# CPU.net
KiCad netlist of a schematic drawn in Altium Designer
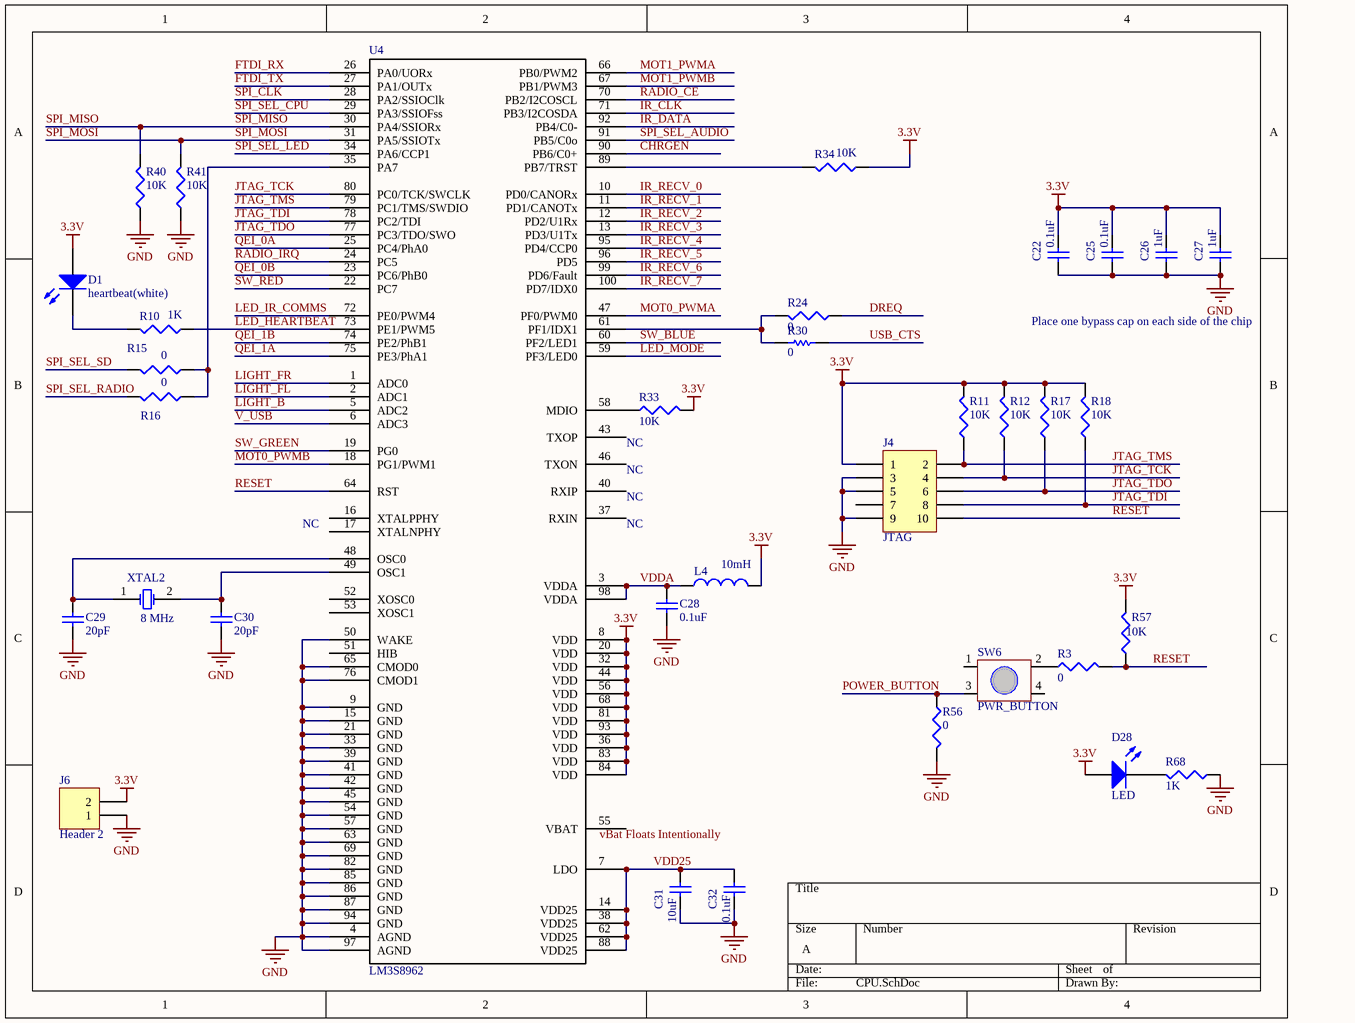
[diagram p0: CPU.SchDoc]

(export (version "E")
  (design (tool "Eeschema 10.0.6"))
  (components
    (comp (ref "C22")
      (value "0.1uF")
      (footprint "CAPC1005L")
      (description "Capacitor (Semiconductor SIM Model)")
      (fields (field (name "Comment") "Cap Semi") (field (name "PUBLISHER") "Altium Limited"))
      (libsource (lib "Miscellaneous Devices") (part "Cap Semi"))
    )
    (comp (ref "C25")
      (value "0.1uF")
      (footprint "CAPC1005L")
      (description "Capacitor (Semiconductor SIM Model)")
      (fields (field (name "Comment") "Cap Semi") (field (name "PUBLISHER") "Altium Limited"))
      (libsource (lib "Miscellaneous Devices") (part "Cap Semi"))
    )
    (comp (ref "C26")
      (value "1uF")
      (footprint "CAPC1608L")
      (description "Capacitor (Semiconductor SIM Model)")
      (fields (field (name "Comment") "Cap Semi") (field (name "PUBLISHER") "Altium Limited"))
      (libsource (lib "Miscellaneous Devices") (part "Cap Semi"))
    )
    (comp (ref "C27")
      (value "1uF")
      (footprint "CAPC1608L")
      (description "Capacitor (Semiconductor SIM Model)")
      (fields (field (name "Comment") "Cap Semi") (field (name "PUBLISHER") "Altium Limited"))
      (libsource (lib "Miscellaneous Devices") (part "Cap Semi"))
    )
    (comp (ref "C28")
      (value "0.1uF")
      (footprint "CAPC1005L")
      (description "Capacitor (Semiconductor SIM Model)")
      (fields (field (name "Comment") "Cap Semi") (field (name "PUBLISHER") "Altium Limited"))
      (libsource (lib "Miscellaneous Devices") (part "Cap Semi"))
    )
    (comp (ref "C29")
      (value "20pF")
      (footprint "CAPC1005L")
      (description "Capacitor (Semiconductor SIM Model)")
      (fields (field (name "Comment") "Cap Semi") (field (name "PUBLISHER") "Altium Limited"))
      (libsource (lib "Miscellaneous Devices") (part "Cap Semi"))
    )
    (comp (ref "C30")
      (value "20pF")
      (footprint "CAPC1005L")
      (description "Capacitor (Semiconductor SIM Model)")
      (fields (field (name "Comment") "Cap Semi") (field (name "PUBLISHER") "Altium Limited"))
      (libsource (lib "Miscellaneous Devices") (part "Cap Semi"))
    )
    (comp (ref "C31")
      (value "10uF")
      (footprint "CAPC1608L")
      (description "Capacitor (Semiconductor SIM Model)")
      (fields (field (name "Comment") "Cap Semi") (field (name "PUBLISHER") "Altium Limited"))
      (libsource (lib "Miscellaneous Devices") (part "Cap Semi"))
    )
    (comp (ref "C32")
      (value "0.1uF")
      (footprint "CAPC1005L")
      (description "Capacitor (Semiconductor SIM Model)")
      (fields (field (name "Comment") "Cap Semi") (field (name "PUBLISHER") "Altium Limited"))
      (libsource (lib "Miscellaneous Devices") (part "Cap Semi"))
    )
    (comp (ref "D1")
      (value "heartbeat(white)")
      (footprint "INDC2012L")
      (description "Typical RED, GREEN, YELLOW, AMBER GaAs LED")
      (fields (field (name "PUBLISHER") "Altium Limited"))
      (libsource (lib "Miscellaneous Devices") (part "LED2"))
    )
    (comp (ref "D28") (value "LED") (footprint "SurfaceMount(603)") (libsource (lib "mrone") (part "LED")))
    (comp (ref "J4")
      (value "JTAG")
      (footprint "JTAG-10")
      (description "Header, 5-Pin, Dual row, Right Angle")
      (fields (field (name "PUBLISHER") "Altium Limited"))
      (libsource (lib "Miscellaneous Connectors") (part "Header 5X2H"))
    )
    (comp (ref "J6")
      (value "Header 2")
      (footprint "HDR1X2")
      (description "Header, 2-Pin")
      (fields (field (name "PUBLISHER") "Altium Limited"))
      (libsource (lib "Miscellaneous Connectors") (part "Header 2"))
    )
    (comp (ref "L4")
      (value "10mH")
      (footprint "INDC2012L")
      (description "Inductor")
      (fields (field (name "PUBLISHER") "Altium Limited"))
      (libsource (lib "Miscellaneous Devices") (part "Inductor"))
    )
    (comp (ref "R3")
      (value "0")
      (footprint "RESC1608L")
      (description "Resistor")
      (fields (field (name "Comment") "Res3") (field (name "PUBLISHER") "Altium Limited"))
      (libsource (lib "Miscellaneous Devices") (part "Res3"))
    )
    (comp (ref "R10")
      (value "1K")
      (footprint "RESC1608L")
      (description "Resistor")
      (fields (field (name "Comment") "Res3") (field (name "PUBLISHER") "Altium Limited"))
      (libsource (lib "Miscellaneous Devices") (part "Res3"))
    )
    (comp (ref "R11")
      (value "10K")
      (footprint "RESC1608L")
      (description "Resistor")
      (fields (field (name "Comment") "Res3") (field (name "PUBLISHER") "Altium Limited"))
      (libsource (lib "Miscellaneous Devices") (part "Res3"))
    )
    (comp (ref "R12")
      (value "10K")
      (footprint "RESC1608L")
      (description "Resistor")
      (fields (field (name "Comment") "Res3") (field (name "PUBLISHER") "Altium Limited"))
      (libsource (lib "Miscellaneous Devices") (part "Res3"))
    )
    (comp (ref "R15")
      (value "0")
      (footprint "RESC1608L")
      (description "Resistor")
      (fields (field (name "Comment") "Res3") (field (name "PUBLISHER") "Altium Limited"))
      (libsource (lib "Miscellaneous Devices") (part "Res3"))
    )
    (comp (ref "R16")
      (value "0")
      (footprint "RESC1608L")
      (description "Resistor")
      (fields (field (name "Comment") "Res3") (field (name "PUBLISHER") "Altium Limited"))
      (libsource (lib "Miscellaneous Devices") (part "Res3"))
    )
    (comp (ref "R17")
      (value "10K")
      (footprint "RESC1608L")
      (description "Resistor")
      (fields (field (name "Comment") "Res3") (field (name "PUBLISHER") "Altium Limited"))
      (libsource (lib "Miscellaneous Devices") (part "Res3"))
    )
    (comp (ref "R18")
      (value "10K")
      (footprint "RESC1608L")
      (description "Resistor")
      (fields (field (name "Comment") "Res3") (field (name "PUBLISHER") "Altium Limited"))
      (libsource (lib "Miscellaneous Devices") (part "Res3"))
    )
    (comp (ref "R24")
      (value "0")
      (footprint "RESC1608L")
      (description "Resistor")
      (fields (field (name "Comment") "Res3") (field (name "PUBLISHER") "Altium Limited"))
      (libsource (lib "Miscellaneous Devices") (part "Res3"))
    )
    (comp (ref "R30")
      (value "0")
      (footprint "RESC1608L")
      (description "Resistor")
      (fields (field (name "PUBLISHER") "Altium Limited"))
      (libsource (lib "Miscellaneous Devices") (part "Res1"))
    )
    (comp (ref "R33")
      (value "10K")
      (footprint "RESC1608L")
      (description "Resistor")
      (fields (field (name "Comment") "Res3") (field (name "PUBLISHER") "Altium Limited"))
      (libsource (lib "Miscellaneous Devices") (part "Res3"))
    )
    (comp (ref "R34")
      (value "10K")
      (footprint "RESC1608L")
      (description "Resistor")
      (fields (field (name "Comment") "Res3") (field (name "PUBLISHER") "Altium Limited"))
      (libsource (lib "Miscellaneous Devices") (part "Res3"))
    )
    (comp (ref "R40")
      (value "10K")
      (footprint "RESC1608L")
      (description "Resistor")
      (fields (field (name "Comment") "Res3") (field (name "PUBLISHER") "Altium Limited"))
      (libsource (lib "Miscellaneous Devices") (part "Res3"))
    )
    (comp (ref "R41")
      (value "10K")
      (footprint "RESC1608L")
      (description "Resistor")
      (fields (field (name "Comment") "Res3") (field (name "PUBLISHER") "Altium Limited"))
      (libsource (lib "Miscellaneous Devices") (part "Res3"))
    )
    (comp (ref "R56")
      (value "0")
      (footprint "RESC1608L")
      (description "Resistor")
      (fields (field (name "Comment") "Res3") (field (name "PUBLISHER") "Altium Limited"))
      (libsource (lib "Miscellaneous Devices") (part "Res3"))
    )
    (comp (ref "R57")
      (value "10K")
      (footprint "RESC1608L")
      (description "Resistor")
      (fields (field (name "Comment") "Res3") (field (name "PUBLISHER") "Altium Limited"))
      (libsource (lib "Miscellaneous Devices") (part "Res3"))
    )
    (comp (ref "R68")
      (value "1K")
      (footprint "RESC1608L")
      (description "Resistor")
      (fields (field (name "Comment") "Res3") (field (name "PUBLISHER") "Altium Limited"))
      (libsource (lib "Miscellaneous Devices") (part "Res3"))
    )
    (comp (ref "SW6")
      (value "PWR_BUTTON")
      (footprint "SwitchTall-TL330")
      (libsource (lib "mrone") (part "Switch-TL330"))
    )
    (comp (ref "U4")
      (value "LM3S8962")
      (footprint "LQFP-100")
      (libsource (lib "Schematic Components") (part "LM3S8962"))
    )
    (comp (ref "XTAL2")
      (value "8 MHz")
      (footprint "RESC5025L")
      (description "Crystal Oscillator")
      (fields (field (name "PUBLISHER") "Altium Limited"))
      (libsource (lib "Miscellaneous Devices") (part "XTAL"))
    )
  )
  (nets
    (net (code "1") (name "/CHRGEN") (class "Default")
      (node (ref "U4") (pin "90") (pinfunction "PB6/C0+_90") (pintype "passive"))
    )
    (net (code "2") (name "/DREQ") (class "Default")
      (node (ref "R24") (pin "2") (pinfunction "2_2") (pintype "passive"))
    )
    (net (code "3") (name "/FTDI_RX") (class "Default")
      (node (ref "U4") (pin "26") (pinfunction "PA0/UORx_26") (pintype "passive"))
    )
    (net (code "4") (name "/FTDI_TX") (class "Default")
      (node (ref "U4") (pin "27") (pinfunction "PA1/OUTx_27") (pintype "passive"))
    )
    (net (code "5") (name "/IR_CLK") (class "Default")
      (node (ref "U4") (pin "71") (pinfunction "PB3/I2COSDA_71") (pintype "passive"))
    )
    (net (code "6") (name "/IR_DATA") (class "Default")
      (node (ref "U4") (pin "92") (pinfunction "PB4/C0-_92") (pintype "passive"))
    )
    (net (code "7") (name "/IR_RECV_0") (class "Default")
      (node (ref "U4") (pin "10") (pinfunction "PD0/CANORx_10") (pintype "passive"))
    )
    (net (code "8") (name "/IR_RECV_1") (class "Default")
      (node (ref "U4") (pin "11") (pinfunction "PD1/CANOTx_11") (pintype "passive"))
    )
    (net (code "9") (name "/IR_RECV_2") (class "Default")
      (node (ref "U4") (pin "12") (pinfunction "PD2/U1Rx_12") (pintype "passive"))
    )
    (net (code "10") (name "/IR_RECV_3") (class "Default")
      (node (ref "U4") (pin "13") (pinfunction "PD3/U1Tx_13") (pintype "passive"))
    )
    (net (code "11") (name "/IR_RECV_4") (class "Default")
      (node (ref "U4") (pin "95") (pinfunction "PD4/CCP0_95") (pintype "passive"))
    )
    (net (code "12") (name "/IR_RECV_5") (class "Default")
      (node (ref "U4") (pin "96") (pinfunction "PD5_96") (pintype "passive"))
    )
    (net (code "13") (name "/IR_RECV_6") (class "Default")
      (node (ref "U4") (pin "99") (pinfunction "PD6/Fault_99") (pintype "passive"))
    )
    (net (code "14") (name "/IR_RECV_7") (class "Default")
      (node (ref "U4") (pin "100") (pinfunction "PD7/IDX0_100") (pintype "passive"))
    )
    (net (code "15") (name "/JTAG_TCK") (class "Default")
      (node (ref "J4") (pin "4") (pinfunction "4_4") (pintype "passive"))
      (node (ref "R12") (pin "1") (pinfunction "1_1") (pintype "passive"))
      (node (ref "U4") (pin "80") (pinfunction "PC0/TCK/SWCLK_80") (pintype "passive"))
    )
    (net (code "16") (name "/JTAG_TDI") (class "Default")
      (node (ref "J4") (pin "8") (pinfunction "8_8") (pintype "passive"))
      (node (ref "R18") (pin "1") (pinfunction "1_1") (pintype "passive"))
      (node (ref "U4") (pin "78") (pinfunction "PC2/TDI_78") (pintype "passive"))
    )
    (net (code "17") (name "/JTAG_TDO") (class "Default")
      (node (ref "J4") (pin "6") (pinfunction "6_6") (pintype "passive"))
      (node (ref "R17") (pin "1") (pinfunction "1_1") (pintype "passive"))
      (node (ref "U4") (pin "77") (pinfunction "PC3/TDO/SWO_77") (pintype "passive"))
    )
    (net (code "18") (name "/JTAG_TMS") (class "Default")
      (node (ref "J4") (pin "2") (pinfunction "2_2") (pintype "passive"))
      (node (ref "R11") (pin "1") (pinfunction "1_1") (pintype "passive"))
      (node (ref "U4") (pin "79") (pinfunction "PC1/TMS/SWDIO_79") (pintype "passive"))
    )
    (net (code "19") (name "/LED_HEARTBEAT") (class "Default")
      (node (ref "R10") (pin "1") (pinfunction "1_1") (pintype "passive"))
      (node (ref "U4") (pin "73") (pinfunction "PE1/PWM5_73") (pintype "passive"))
    )
    (net (code "20") (name "/LED_IR_COMMS") (class "Default")
      (node (ref "U4") (pin "72") (pinfunction "PE0/PWM4_72") (pintype "passive"))
    )
    (net (code "21") (name "/LED_MODE") (class "Default")
      (node (ref "U4") (pin "59") (pinfunction "PF3/LED0_59") (pintype "passive"))
    )
    (net (code "22") (name "/LIGHT_B") (class "Default")
      (node (ref "U4") (pin "5") (pinfunction "ADC2_5") (pintype "passive"))
    )
    (net (code "23") (name "/LIGHT_FL") (class "Default")
      (node (ref "U4") (pin "2") (pinfunction "ADC1_2") (pintype "passive"))
    )
    (net (code "24") (name "/LIGHT_FR") (class "Default")
      (node (ref "U4") (pin "1") (pinfunction "ADC0_1") (pintype "passive"))
    )
    (net (code "25") (name "/MOT0_PWMA") (class "Default")
      (node (ref "U4") (pin "47") (pinfunction "PF0/PWM0_47") (pintype "passive"))
    )
    (net (code "26") (name "/MOT0_PWMB") (class "Default")
      (node (ref "U4") (pin "18") (pinfunction "PG1/PWM1_18") (pintype "passive"))
    )
    (net (code "27") (name "/MOT1_PWMA") (class "Default")
      (node (ref "U4") (pin "66") (pinfunction "PB0/PWM2_66") (pintype "passive"))
    )
    (net (code "28") (name "/MOT1_PWMB") (class "Default")
      (node (ref "U4") (pin "67") (pinfunction "PB1/PWM3_67") (pintype "passive"))
    )
    (net (code "29") (name "/POWER_BUTTON") (class "Default")
      (node (ref "R56") (pin "1") (pinfunction "1_1") (pintype "passive"))
      (node (ref "SW6") (pin "3") (pinfunction "3_3") (pintype "passive"))
    )
    (net (code "30") (name "/QEI_0A") (class "Default")
      (node (ref "U4") (pin "25") (pinfunction "PC4/PhA0_25") (pintype "passive"))
    )
    (net (code "31") (name "/QEI_0B") (class "Default")
      (node (ref "U4") (pin "23") (pinfunction "PC6/PhB0_23") (pintype "passive"))
    )
    (net (code "32") (name "/QEI_1A") (class "Default")
      (node (ref "U4") (pin "75") (pinfunction "PE3/PhA1_75") (pintype "passive"))
    )
    (net (code "33") (name "/QEI_1B") (class "Default")
      (node (ref "U4") (pin "74") (pinfunction "PE2/PhB1_74") (pintype "passive"))
    )
    (net (code "34") (name "/RADIO_CE") (class "Default")
      (node (ref "U4") (pin "70") (pinfunction "PB2/I2COSCL_70") (pintype "passive"))
    )
    (net (code "35") (name "/RADIO_IRQ") (class "Default")
      (node (ref "U4") (pin "24") (pinfunction "PC5_24") (pintype "passive"))
    )
    (net (code "36") (name "/RESET") (class "Default")
      (node (ref "J4") (pin "10") (pinfunction "10_10") (pintype "passive"))
      (node (ref "R3") (pin "2") (pinfunction "2_2") (pintype "passive"))
      (node (ref "R57") (pin "1") (pinfunction "1_1") (pintype "passive"))
      (node (ref "U4") (pin "64") (pinfunction "RST_64") (pintype "passive"))
    )
    (net (code "37") (name "/SPI_CLK") (class "Default")
      (node (ref "U4") (pin "28") (pinfunction "PA2/SSIOClk_28") (pintype "passive"))
    )
    (net (code "38") (name "/SPI_MISO") (class "Default")
      (node (ref "R40") (pin "2") (pinfunction "2_2") (pintype "passive"))
      (node (ref "U4") (pin "30") (pinfunction "PA4/SSIORx_30") (pintype "passive"))
    )
    (net (code "39") (name "/SPI_MOSI") (class "Default")
      (node (ref "R41") (pin "2") (pinfunction "2_2") (pintype "passive"))
      (node (ref "U4") (pin "31") (pinfunction "PA5/SSIOTx_31") (pintype "passive"))
    )
    (net (code "40") (name "/SPI_SEL_AUDIO") (class "Default")
      (node (ref "U4") (pin "91") (pinfunction "PB5/C0o_91") (pintype "passive"))
    )
    (net (code "41") (name "/SPI_SEL_CPU") (class "Default")
      (node (ref "U4") (pin "29") (pinfunction "PA3/SSIOFss_29") (pintype "passive"))
    )
    (net (code "42") (name "/SPI_SEL_LED") (class "Default")
      (node (ref "U4") (pin "34") (pinfunction "PA6/CCP1_34") (pintype "passive"))
    )
    (net (code "43") (name "/SPI_SEL_RADIO") (class "Default")
      (node (ref "R16") (pin "2") (pinfunction "2_2") (pintype "passive"))
    )
    (net (code "44") (name "/SPI_SEL_SD") (class "Default")
      (node (ref "R15") (pin "2") (pinfunction "2_2") (pintype "passive"))
    )
    (net (code "45") (name "/SW_BLUE") (class "Default")
      (node (ref "U4") (pin "60") (pinfunction "PF2/LED1_60") (pintype "passive"))
    )
    (net (code "46") (name "/SW_GREEN") (class "Default")
      (node (ref "U4") (pin "19") (pinfunction "PG0_19") (pintype "passive"))
    )
    (net (code "47") (name "/SW_RED") (class "Default")
      (node (ref "U4") (pin "22") (pinfunction "PC7_22") (pintype "passive"))
    )
    (net (code "48") (name "/USB_CTS") (class "Default")
      (node (ref "R30") (pin "2") (pinfunction "2_2") (pintype "passive"))
    )
    (net (code "49") (name "/VDD25") (class "Default")
      (node (ref "C31") (pin "2") (pinfunction "2_2") (pintype "passive"))
      (node (ref "C32") (pin "2") (pinfunction "2_2") (pintype "passive"))
      (node (ref "U4") (pin "14") (pinfunction "VDD25_14") (pintype "passive"))
      (node (ref "U4") (pin "38") (pinfunction "VDD25_38") (pintype "passive"))
      (node (ref "U4") (pin "62") (pinfunction "VDD25_62") (pintype "passive"))
      (node (ref "U4") (pin "7") (pinfunction "LDO_7") (pintype "passive"))
      (node (ref "U4") (pin "88") (pinfunction "VDD25_88") (pintype "passive"))
    )
    (net (code "50") (name "/VDDA") (class "Default")
      (node (ref "C28") (pin "2") (pinfunction "2_2") (pintype "passive"))
      (node (ref "L4") (pin "1") (pinfunction "1_1") (pintype "passive"))
      (node (ref "U4") (pin "3") (pinfunction "VDDA_3") (pintype "passive"))
      (node (ref "U4") (pin "98") (pinfunction "VDDA_98") (pintype "passive"))
    )
    (net (code "51") (name "/V_USB") (class "Default")
      (node (ref "U4") (pin "6") (pinfunction "ADC3_6") (pintype "passive"))
    )
    (net (code "52") (name "3.3V") (class "Default")
      (node (ref "C22") (pin "2") (pinfunction "2_2") (pintype "passive"))
      (node (ref "C25") (pin "2") (pinfunction "2_2") (pintype "passive"))
      (node (ref "C26") (pin "2") (pinfunction "2_2") (pintype "passive"))
      (node (ref "C27") (pin "2") (pinfunction "2_2") (pintype "passive"))
      (node (ref "D1") (pin "1") (pinfunction "A_1") (pintype "passive"))
      (node (ref "D28") (pin "1") (pinfunction "A_1") (pintype "passive"))
      (node (ref "J4") (pin "1") (pinfunction "1_1") (pintype "passive"))
      (node (ref "J6") (pin "2") (pinfunction "2_2") (pintype "passive"))
      (node (ref "L4") (pin "2") (pinfunction "2_2") (pintype "passive"))
      (node (ref "R11") (pin "2") (pinfunction "2_2") (pintype "passive"))
      (node (ref "R12") (pin "2") (pinfunction "2_2") (pintype "passive"))
      (node (ref "R17") (pin "2") (pinfunction "2_2") (pintype "passive"))
      (node (ref "R18") (pin "2") (pinfunction "2_2") (pintype "passive"))
      (node (ref "R33") (pin "2") (pinfunction "2_2") (pintype "passive"))
      (node (ref "R34") (pin "1") (pinfunction "1_1") (pintype "passive"))
      (node (ref "R57") (pin "2") (pinfunction "2_2") (pintype "passive"))
      (node (ref "U4") (pin "20") (pinfunction "VDD_20") (pintype "passive"))
      (node (ref "U4") (pin "32") (pinfunction "VDD_32") (pintype "passive"))
      (node (ref "U4") (pin "36") (pinfunction "VDD_36") (pintype "passive"))
      (node (ref "U4") (pin "44") (pinfunction "VDD_44") (pintype "passive"))
      (node (ref "U4") (pin "56") (pinfunction "VDD_56") (pintype "passive"))
      (node (ref "U4") (pin "68") (pinfunction "VDD_68") (pintype "passive"))
      (node (ref "U4") (pin "8") (pinfunction "VDD_8") (pintype "passive"))
      (node (ref "U4") (pin "81") (pinfunction "VDD_81") (pintype "passive"))
      (node (ref "U4") (pin "83") (pinfunction "VDD_83") (pintype "passive"))
      (node (ref "U4") (pin "84") (pinfunction "VDD_84") (pintype "passive"))
      (node (ref "U4") (pin "93") (pinfunction "VDD_93") (pintype "passive"))
    )
    (net (code "53") (name "GND") (class "Default")
      (node (ref "C22") (pin "1") (pinfunction "1_1") (pintype "passive"))
      (node (ref "C25") (pin "1") (pinfunction "1_1") (pintype "passive"))
      (node (ref "C26") (pin "1") (pinfunction "1_1") (pintype "passive"))
      (node (ref "C27") (pin "1") (pinfunction "1_1") (pintype "passive"))
      (node (ref "C28") (pin "1") (pinfunction "1_1") (pintype "passive"))
      (node (ref "C29") (pin "1") (pinfunction "1_1") (pintype "passive"))
      (node (ref "C30") (pin "1") (pinfunction "1_1") (pintype "passive"))
      (node (ref "C31") (pin "1") (pinfunction "1_1") (pintype "passive"))
      (node (ref "C32") (pin "1") (pinfunction "1_1") (pintype "passive"))
      (node (ref "J4") (pin "3") (pinfunction "3_3") (pintype "passive"))
      (node (ref "J4") (pin "5") (pinfunction "5_5") (pintype "passive"))
      (node (ref "J4") (pin "9") (pinfunction "9_9") (pintype "passive"))
      (node (ref "J6") (pin "1") (pinfunction "1_1") (pintype "passive"))
      (node (ref "R40") (pin "1") (pinfunction "1_1") (pintype "passive"))
      (node (ref "R41") (pin "1") (pinfunction "1_1") (pintype "passive"))
      (node (ref "R56") (pin "2") (pinfunction "2_2") (pintype "passive"))
      (node (ref "R68") (pin "1") (pinfunction "1_1") (pintype "passive"))
      (node (ref "U4") (pin "15") (pinfunction "GND_15") (pintype "passive"))
      (node (ref "U4") (pin "21") (pinfunction "GND_21") (pintype "passive"))
      (node (ref "U4") (pin "33") (pinfunction "GND_33") (pintype "passive"))
      (node (ref "U4") (pin "39") (pinfunction "GND_39") (pintype "passive"))
      (node (ref "U4") (pin "4") (pinfunction "AGND_4") (pintype "passive"))
      (node (ref "U4") (pin "41") (pinfunction "GND_41") (pintype "passive"))
      (node (ref "U4") (pin "42") (pinfunction "GND_42") (pintype "passive"))
      (node (ref "U4") (pin "45") (pinfunction "GND_45") (pintype "passive"))
      (node (ref "U4") (pin "50") (pinfunction "WAKE_50") (pintype "passive"))
      (node (ref "U4") (pin "54") (pinfunction "GND_54") (pintype "passive"))
      (node (ref "U4") (pin "57") (pinfunction "GND_57") (pintype "passive"))
      (node (ref "U4") (pin "63") (pinfunction "GND_63") (pintype "passive"))
      (node (ref "U4") (pin "65") (pinfunction "CMOD0_65") (pintype "passive"))
      (node (ref "U4") (pin "69") (pinfunction "GND_69") (pintype "passive"))
      (node (ref "U4") (pin "76") (pinfunction "CMOD1_76") (pintype "passive"))
      (node (ref "U4") (pin "82") (pinfunction "GND_82") (pintype "passive"))
      (node (ref "U4") (pin "85") (pinfunction "GND_85") (pintype "passive"))
      (node (ref "U4") (pin "86") (pinfunction "GND_86") (pintype "passive"))
      (node (ref "U4") (pin "87") (pinfunction "GND_87") (pintype "passive"))
      (node (ref "U4") (pin "9") (pinfunction "GND_9") (pintype "passive"))
      (node (ref "U4") (pin "94") (pinfunction "GND_94") (pintype "passive"))
      (node (ref "U4") (pin "97") (pinfunction "AGND_97") (pintype "passive"))
    )
    (net (code "54") (name "Net-(D1-K)") (class "Default")
      (node (ref "D1") (pin "2") (pinfunction "K_2") (pintype "passive"))
      (node (ref "R10") (pin "2") (pinfunction "2_2") (pintype "passive"))
    )
    (net (code "55") (name "Net-(D28-K)") (class "Default")
      (node (ref "D28") (pin "2") (pinfunction "K_2") (pintype "passive"))
      (node (ref "R68") (pin "2") (pinfunction "2_2") (pintype "passive"))
    )
    (net (code "56") (name "Net-(R3-Pad1)") (class "Default")
      (node (ref "R3") (pin "1") (pinfunction "1_1") (pintype "passive"))
      (node (ref "SW6") (pin "2") (pinfunction "2_2") (pintype "passive"))
    )
    (net (code "57") (name "Net-(U4-MDIO)") (class "Default")
      (node (ref "R33") (pin "1") (pinfunction "1_1") (pintype "passive"))
      (node (ref "U4") (pin "58") (pinfunction "MDIO_58") (pintype "passive"))
    )
    (net (code "58") (name "Net-(U4-OSC0)") (class "Default")
      (node (ref "C29") (pin "2") (pinfunction "2_2") (pintype "passive"))
      (node (ref "U4") (pin "48") (pinfunction "OSC0_48") (pintype "passive"))
      (node (ref "XTAL2") (pin "1") (pinfunction "OSC1_1") (pintype "passive"))
    )
    (net (code "59") (name "Net-(U4-OSC1)") (class "Default")
      (node (ref "C30") (pin "2") (pinfunction "2_2") (pintype "passive"))
      (node (ref "U4") (pin "49") (pinfunction "OSC1_49") (pintype "passive"))
      (node (ref "XTAL2") (pin "2") (pinfunction "OSC2_2") (pintype "passive"))
    )
    (net (code "60") (name "Net-(U4-PA7)") (class "Default")
      (node (ref "R15") (pin "1") (pinfunction "1_1") (pintype "passive"))
      (node (ref "R16") (pin "1") (pinfunction "1_1") (pintype "passive"))
      (node (ref "U4") (pin "35") (pinfunction "PA7_35") (pintype "passive"))
    )
    (net (code "61") (name "Net-(U4-PB7{slash}TRST)") (class "Default")
      (node (ref "R34") (pin "2") (pinfunction "2_2") (pintype "passive"))
      (node (ref "U4") (pin "89") (pinfunction "PB7/TRST_89") (pintype "passive"))
    )
    (net (code "62") (name "Net-(U4-PF1{slash}IDX1)") (class "Default")
      (node (ref "R24") (pin "1") (pinfunction "1_1") (pintype "passive"))
      (node (ref "R30") (pin "1") (pinfunction "1_1") (pintype "passive"))
      (node (ref "U4") (pin "61") (pinfunction "PF1/IDX1_61") (pintype "passive"))
    )
    (net (code "63") (name "unconnected-(J4-Pad7)") (class "Default")
      (node (ref "J4") (pin "7") (pinfunction "7_7") (pintype "passive"))
    )
    (net (code "64") (name "unconnected-(SW6-Pad1)") (class "Default")
      (node (ref "SW6") (pin "1") (pinfunction "1_1") (pintype "passive"))
    )
    (net (code "65") (name "unconnected-(SW6-Pad4)") (class "Default")
      (node (ref "SW6") (pin "4") (pinfunction "4_4") (pintype "passive"))
    )
    (net (code "66") (name "unconnected-(U4-HIB-Pad51)") (class "Default")
      (node (ref "U4") (pin "51") (pinfunction "HIB_51") (pintype "passive"))
    )
    (net (code "67") (name "unconnected-(U4-RXIN-Pad37)") (class "Default")
      (node (ref "U4") (pin "37") (pinfunction "RXIN_37") (pintype "passive"))
    )
    (net (code "68") (name "unconnected-(U4-RXIP-Pad40)") (class "Default")
      (node (ref "U4") (pin "40") (pinfunction "RXIP_40") (pintype "passive"))
    )
    (net (code "69") (name "unconnected-(U4-TXON-Pad46)") (class "Default")
      (node (ref "U4") (pin "46") (pinfunction "TXON_46") (pintype "passive"))
    )
    (net (code "70") (name "unconnected-(U4-TXOP-Pad43)") (class "Default")
      (node (ref "U4") (pin "43") (pinfunction "TXOP_43") (pintype "passive"))
    )
    (net (code "71") (name "unconnected-(U4-VBAT-Pad55)") (class "Default")
      (node (ref "U4") (pin "55") (pinfunction "VBAT_55") (pintype "passive"))
    )
    (net (code "72") (name "unconnected-(U4-XOSC0-Pad52)") (class "Default")
      (node (ref "U4") (pin "52") (pinfunction "XOSC0_52") (pintype "passive"))
    )
    (net (code "73") (name "unconnected-(U4-XOSC1-Pad53)") (class "Default")
      (node (ref "U4") (pin "53") (pinfunction "XOSC1_53") (pintype "passive"))
    )
    (net (code "74") (name "unconnected-(U4-XTALNPHY-Pad17)") (class "Default")
      (node (ref "U4") (pin "17") (pinfunction "XTALNPHY_17") (pintype "passive"))
    )
    (net (code "75") (name "unconnected-(U4-XTALPPHY-Pad16)") (class "Default")
      (node (ref "U4") (pin "16") (pinfunction "XTALPPHY_16") (pintype "passive"))
    )
  )
)
